# USART.net
KiCad netlist of a schematic drawn in Altium Designer
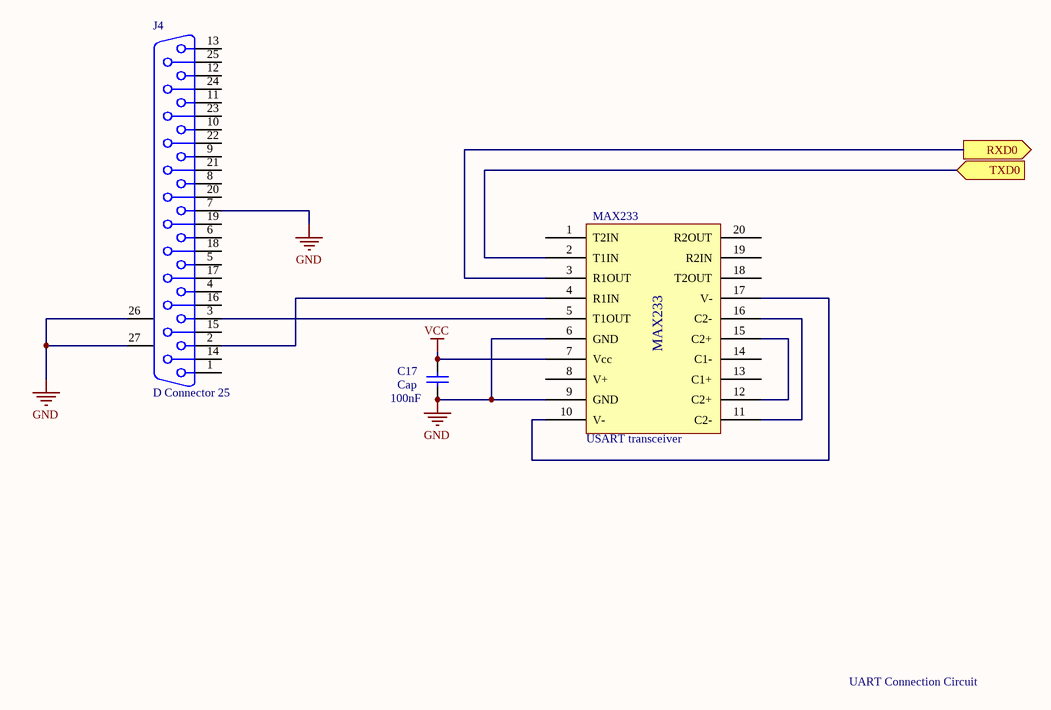
[diagram p0: USART.SchDoc]

(export (version "E")
  (design (tool "Eeschema 10.0.6"))
  (components
    (comp (ref "C17")
      (value "Cap")
      (footprint "C1210")
      (description "Capacitor (Semiconductor SIM Model)")
      (fields (field (name "ALTIUM_VALUE") "100nF") (field (name "PUBLISHER") "Altium Limited"))
      (libsource (lib "Miscellaneous Devices") (part "Cap Semi"))
    )
    (comp (ref "J4")
      (value "D Connector 25")
      (footprint "DSUB1.385-2H25A")
      (description "Receptacle Assembly, 25 Position, Right Angle")
      (fields (field (name "PUBLISHER") "Altium Limited"))
      (libsource (lib "Miscellaneous Connectors") (part "D Connector 25"))
    )
    (comp (ref "MAX233")
      (value "USART transceiver")
      (footprint "MAX233 SOIC 20-PIN")
      (description "Maxim RS232 transceiver")
      (libsource (lib "IIDKLib") (part "MAX233"))
    )
  )
  (nets
    (net (code "1") (name "/RXD0") (class "Default")
      (node (ref "MAX233") (pin "3") (pinfunction "R1OUT_3") (pintype "passive"))
    )
    (net (code "2") (name "/TXD0") (class "Default")
      (node (ref "MAX233") (pin "2") (pinfunction "T1IN_2") (pintype "passive"))
    )
    (net (code "3") (name "GND") (class "Default")
      (node (ref "C17") (pin "2") (pinfunction "2_2") (pintype "passive"))
      (node (ref "J4") (pin "26") (pinfunction "MH1_26") (pintype "passive"))
      (node (ref "J4") (pin "27") (pinfunction "MH2_27") (pintype "passive"))
      (node (ref "J4") (pin "7") (pinfunction "7_7") (pintype "passive"))
      (node (ref "MAX233") (pin "6") (pinfunction "GND_6") (pintype "passive"))
      (node (ref "MAX233") (pin "9") (pinfunction "GND_9") (pintype "passive"))
    )
    (net (code "4") (name "Net-(MAX233-C2+-Pad12)") (class "Default")
      (node (ref "MAX233") (pin "12") (pinfunction "C2+_12") (pintype "passive"))
      (node (ref "MAX233") (pin "15") (pinfunction "C2+_15") (pintype "passive"))
    )
    (net (code "5") (name "Net-(MAX233-C2--Pad11)") (class "Default")
      (node (ref "MAX233") (pin "11") (pinfunction "C2-_11") (pintype "passive"))
      (node (ref "MAX233") (pin "16") (pinfunction "C2-_16") (pintype "passive"))
    )
    (net (code "6") (name "Net-(MAX233-R1IN)") (class "Default")
      (node (ref "J4") (pin "2") (pinfunction "2_2") (pintype "passive"))
      (node (ref "MAX233") (pin "4") (pinfunction "R1IN_4") (pintype "passive"))
    )
    (net (code "7") (name "Net-(MAX233-T1OUT)") (class "Default")
      (node (ref "J4") (pin "3") (pinfunction "3_3") (pintype "passive"))
      (node (ref "MAX233") (pin "5") (pinfunction "T1OUT_5") (pintype "passive"))
    )
    (net (code "8") (name "Net-(MAX233-V--Pad10)") (class "Default")
      (node (ref "MAX233") (pin "10") (pinfunction "V-_10") (pintype "passive"))
      (node (ref "MAX233") (pin "17") (pinfunction "V-_17") (pintype "passive"))
    )
    (net (code "9") (name "VCC") (class "Default")
      (node (ref "C17") (pin "1") (pinfunction "1_1") (pintype "passive"))
      (node (ref "MAX233") (pin "7") (pinfunction "Vcc_7") (pintype "passive"))
    )
    (net (code "10") (name "unconnected-(J4-Pad1)") (class "Default")
      (node (ref "J4") (pin "1") (pinfunction "1_1") (pintype "passive"))
    )
    (net (code "11") (name "unconnected-(J4-Pad4)") (class "Default")
      (node (ref "J4") (pin "4") (pinfunction "4_4") (pintype "passive"))
    )
    (net (code "12") (name "unconnected-(J4-Pad5)") (class "Default")
      (node (ref "J4") (pin "5") (pinfunction "5_5") (pintype "passive"))
    )
    (net (code "13") (name "unconnected-(J4-Pad6)") (class "Default")
      (node (ref "J4") (pin "6") (pinfunction "6_6") (pintype "passive"))
    )
    (net (code "14") (name "unconnected-(J4-Pad8)") (class "Default")
      (node (ref "J4") (pin "8") (pinfunction "8_8") (pintype "passive"))
    )
    (net (code "15") (name "unconnected-(J4-Pad9)") (class "Default")
      (node (ref "J4") (pin "9") (pinfunction "9_9") (pintype "passive"))
    )
    (net (code "16") (name "unconnected-(J4-Pad10)") (class "Default")
      (node (ref "J4") (pin "10") (pinfunction "10_10") (pintype "passive"))
    )
    (net (code "17") (name "unconnected-(J4-Pad11)") (class "Default")
      (node (ref "J4") (pin "11") (pinfunction "11_11") (pintype "passive"))
    )
    (net (code "18") (name "unconnected-(J4-Pad12)") (class "Default")
      (node (ref "J4") (pin "12") (pinfunction "12_12") (pintype "passive"))
    )
    (net (code "19") (name "unconnected-(J4-Pad13)") (class "Default")
      (node (ref "J4") (pin "13") (pinfunction "13_13") (pintype "passive"))
    )
    (net (code "20") (name "unconnected-(J4-Pad14)") (class "Default")
      (node (ref "J4") (pin "14") (pinfunction "14_14") (pintype "passive"))
    )
    (net (code "21") (name "unconnected-(J4-Pad15)") (class "Default")
      (node (ref "J4") (pin "15") (pinfunction "15_15") (pintype "passive"))
    )
    (net (code "22") (name "unconnected-(J4-Pad16)") (class "Default")
      (node (ref "J4") (pin "16") (pinfunction "16_16") (pintype "passive"))
    )
    (net (code "23") (name "unconnected-(J4-Pad17)") (class "Default")
      (node (ref "J4") (pin "17") (pinfunction "17_17") (pintype "passive"))
    )
    (net (code "24") (name "unconnected-(J4-Pad18)") (class "Default")
      (node (ref "J4") (pin "18") (pinfunction "18_18") (pintype "passive"))
    )
    (net (code "25") (name "unconnected-(J4-Pad19)") (class "Default")
      (node (ref "J4") (pin "19") (pinfunction "19_19") (pintype "passive"))
    )
    (net (code "26") (name "unconnected-(J4-Pad20)") (class "Default")
      (node (ref "J4") (pin "20") (pinfunction "20_20") (pintype "passive"))
    )
    (net (code "27") (name "unconnected-(J4-Pad21)") (class "Default")
      (node (ref "J4") (pin "21") (pinfunction "21_21") (pintype "passive"))
    )
    (net (code "28") (name "unconnected-(J4-Pad22)") (class "Default")
      (node (ref "J4") (pin "22") (pinfunction "22_22") (pintype "passive"))
    )
    (net (code "29") (name "unconnected-(J4-Pad23)") (class "Default")
      (node (ref "J4") (pin "23") (pinfunction "23_23") (pintype "passive"))
    )
    (net (code "30") (name "unconnected-(J4-Pad24)") (class "Default")
      (node (ref "J4") (pin "24") (pinfunction "24_24") (pintype "passive"))
    )
    (net (code "31") (name "unconnected-(J4-Pad25)") (class "Default")
      (node (ref "J4") (pin "25") (pinfunction "25_25") (pintype "passive"))
    )
    (net (code "32") (name "unconnected-(MAX233-C1+-Pad13)") (class "Default")
      (node (ref "MAX233") (pin "13") (pinfunction "C1+_13") (pintype "passive"))
    )
    (net (code "33") (name "unconnected-(MAX233-C1--Pad14)") (class "Default")
      (node (ref "MAX233") (pin "14") (pinfunction "C1-_14") (pintype "passive"))
    )
    (net (code "34") (name "unconnected-(MAX233-R2IN-Pad19)") (class "Default")
      (node (ref "MAX233") (pin "19") (pinfunction "R2IN_19") (pintype "passive"))
    )
    (net (code "35") (name "unconnected-(MAX233-R2OUT-Pad20)") (class "Default")
      (node (ref "MAX233") (pin "20") (pinfunction "R2OUT_20") (pintype "passive"))
    )
    (net (code "36") (name "unconnected-(MAX233-T2IN-Pad1)") (class "Default")
      (node (ref "MAX233") (pin "1") (pinfunction "T2IN_1") (pintype "passive"))
    )
    (net (code "37") (name "unconnected-(MAX233-T2OUT-Pad18)") (class "Default")
      (node (ref "MAX233") (pin "18") (pinfunction "T2OUT_18") (pintype "passive"))
    )
    (net (code "38") (name "unconnected-(MAX233-V+-Pad8)") (class "Default")
      (node (ref "MAX233") (pin "8") (pinfunction "V+_8") (pintype "passive"))
    )
  )
)
